# main.net
KiCad netlist of a schematic drawn in EAGLE
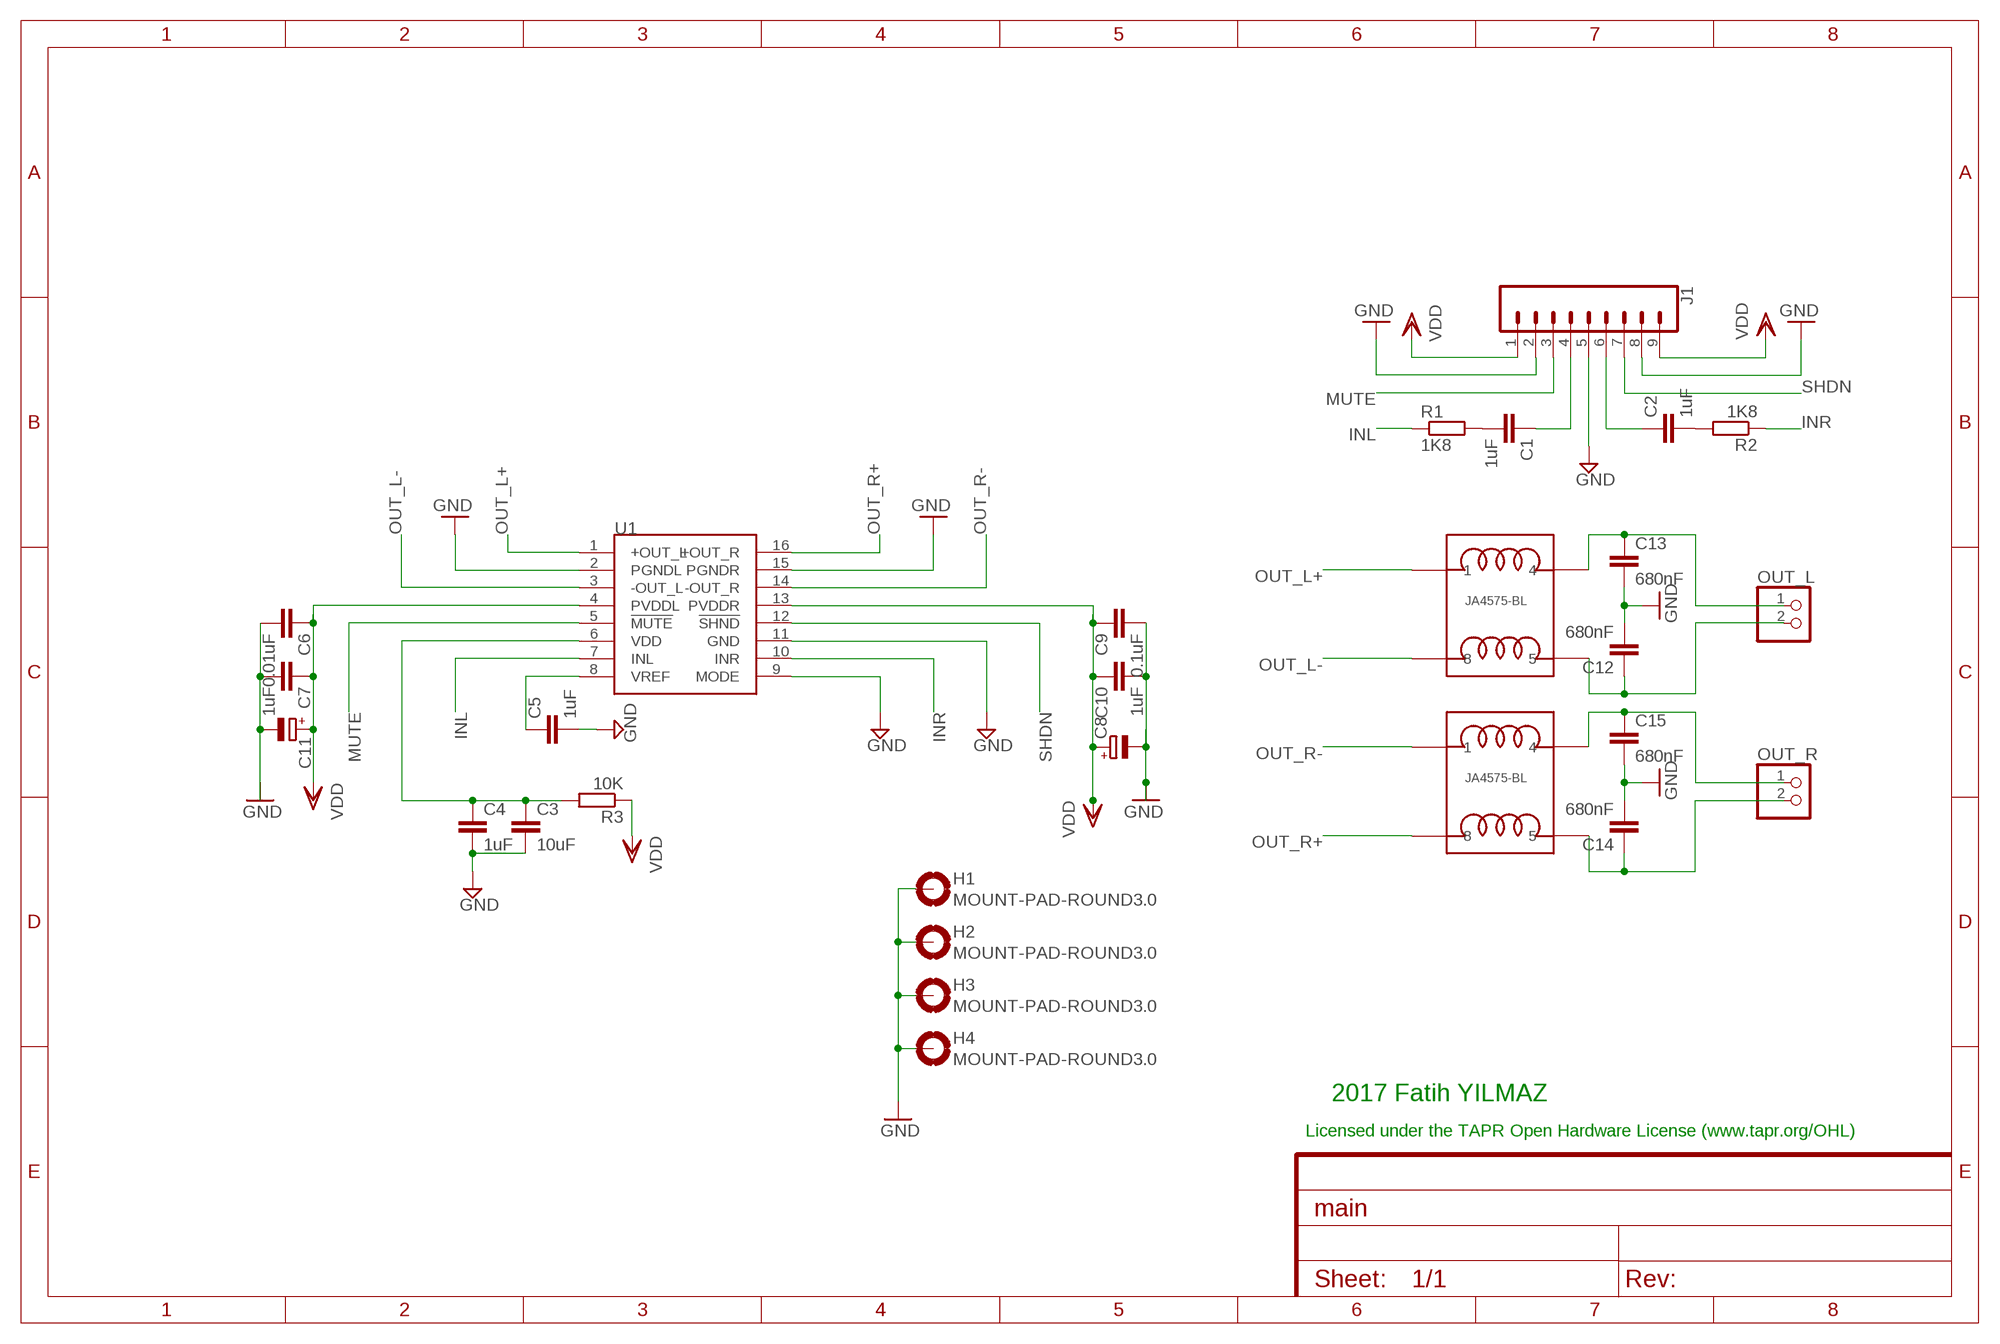
[diagram p0: schematic, sheet 1]

(export (version "E")
  (design (tool "Eeschema 10.0.6"))
  (components
    (comp (ref "C1")
      (value "1uF")
      (footprint "eagle-import:C1206")
      (fields (field (name "MPN") "C0603C105K4PACTU"))
      (libsource (lib "eagle-import") (part "C-EUC1206"))
    )
    (comp (ref "C2")
      (value "1uF")
      (footprint "eagle-import:C1206")
      (fields (field (name "MPN") "C0603C105K4PACTU"))
      (libsource (lib "eagle-import") (part "C-EUC1206"))
    )
    (comp (ref "C3")
      (value "10uF")
      (footprint "eagle-import:C1206")
      (libsource (lib "eagle-import") (part "C-EUC1206"))
    )
    (comp (ref "C4")
      (value "1uF")
      (footprint "eagle-import:C1206")
      (libsource (lib "eagle-import") (part "C-EUC1206"))
    )
    (comp (ref "C5")
      (value "1uF")
      (footprint "eagle-import:C1206")
      (libsource (lib "eagle-import") (part "C-EUC1206"))
    )
    (comp (ref "C6")
      (value "0.01uF")
      (footprint "eagle-import:C1206")
      (libsource (lib "eagle-import") (part "C-EUC1206"))
    )
    (comp (ref "C7")
      (value "1uF")
      (footprint "eagle-import:C1206")
      (libsource (lib "eagle-import") (part "C-EUC1206"))
    )
    (comp (ref "C8")
      (value "CPOL-EUE3.5-8")
      (footprint "eagle-import:E3,5-8")
      (libsource (lib "eagle-import") (part "CPOL-EUE3.5-8"))
    )
    (comp (ref "C9")
      (value "0.1uF")
      (footprint "eagle-import:C1206")
      (libsource (lib "eagle-import") (part "C-EUC1206"))
    )
    (comp (ref "C10")
      (value "1uF")
      (footprint "eagle-import:C1206")
      (libsource (lib "eagle-import") (part "C-EUC1206"))
    )
    (comp (ref "C11")
      (value "CPOL-EUE3.5-8")
      (footprint "eagle-import:E3,5-8")
      (libsource (lib "eagle-import") (part "CPOL-EUE3.5-8"))
    )
    (comp (ref "C12")
      (value "680nF")
      (footprint "eagle-import:C050-045X075")
      (libsource (lib "eagle-import") (part "C-EU050-045X075"))
    )
    (comp (ref "C13")
      (value "680nF")
      (footprint "eagle-import:C050-045X075")
      (libsource (lib "eagle-import") (part "C-EU050-045X075"))
    )
    (comp (ref "C14")
      (value "680nF")
      (footprint "eagle-import:C050-045X075")
      (libsource (lib "eagle-import") (part "C-EU050-045X075"))
    )
    (comp (ref "C15")
      (value "680nF")
      (footprint "eagle-import:C050-045X075")
      (libsource (lib "eagle-import") (part "C-EU050-045X075"))
    )
    (comp (ref "H1")
      (value "MOUNT-PAD-ROUND3.0")
      (footprint "eagle-import:3,0-PAD")
      (libsource (lib "eagle-import") (part "MOUNT-PAD-ROUND3.0"))
    )
    (comp (ref "H2")
      (value "MOUNT-PAD-ROUND3.0")
      (footprint "eagle-import:3,0-PAD")
      (libsource (lib "eagle-import") (part "MOUNT-PAD-ROUND3.0"))
    )
    (comp (ref "H3")
      (value "MOUNT-PAD-ROUND3.0")
      (footprint "eagle-import:3,0-PAD")
      (libsource (lib "eagle-import") (part "MOUNT-PAD-ROUND3.0"))
    )
    (comp (ref "H4")
      (value "MOUNT-PAD-ROUND3.0")
      (footprint "eagle-import:3,0-PAD")
      (libsource (lib "eagle-import") (part "MOUNT-PAD-ROUND3.0"))
    )
    (comp (ref "J1")
      (value "CONN_09NO_SILK")
      (footprint "eagle-import:1X09_NO_SILK")
      (libsource (lib "eagle-import") (part "CONN_09NO_SILK"))
    )
    (comp (ref "LEFT_COIL")
      (value "JA4575-BL")
      (footprint "eagle-import:JA4575-BL")
      (libsource (lib "eagle-import") (part "JA4575-BL"))
    )
    (comp (ref "OUT_L")
      (value "PINHD-1X2")
      (footprint "eagle-import:1X02")
      (libsource (lib "eagle-import") (part "PINHD-1X2"))
    )
    (comp (ref "OUT_R")
      (value "PINHD-1X2")
      (footprint "eagle-import:1X02")
      (libsource (lib "eagle-import") (part "PINHD-1X2"))
    )
    (comp (ref "R1")
      (value "1K8")
      (footprint "eagle-import:R1206")
      (libsource (lib "eagle-import") (part "R-EU_R1206"))
    )
    (comp (ref "R2")
      (value "1K8")
      (footprint "eagle-import:R1206")
      (libsource (lib "eagle-import") (part "R-EU_R1206"))
    )
    (comp (ref "R3")
      (value "10K")
      (footprint "eagle-import:R1206")
      (libsource (lib "eagle-import") (part "R-EU_R1206"))
    )
    (comp (ref "RIGHT_COIL")
      (value "JA4575-BL")
      (footprint "eagle-import:JA4575-BL")
      (libsource (lib "eagle-import") (part "JA4575-BL"))
    )
    (comp (ref "U1")
      (value "PAM8403")
      (footprint "eagle-import:SOP-16")
      (libsource (lib "eagle-import") (part "PAM8403"))
    )
  )
  (nets
    (net (code "1") (name "/INL") (class "Default")
      (node (ref "R1") (pin "1") (pinfunction "1_1") (pintype "passive"))
      (node (ref "U1") (pin "7") (pinfunction "INL_7") (pintype "input"))
    )
    (net (code "2") (name "/INR") (class "Default")
      (node (ref "R2") (pin "1") (pinfunction "1_1") (pintype "passive"))
      (node (ref "U1") (pin "10") (pinfunction "INR_10") (pintype "input"))
    )
    (net (code "3") (name "/MUTE") (class "Default")
      (node (ref "J1") (pin "3") (pinfunction "3_3") (pintype "passive"))
      (node (ref "U1") (pin "5") (pinfunction "~{MUTE}_5") (pintype "input"))
    )
    (net (code "4") (name "/OUT_L+") (class "Default")
      (node (ref "LEFT_COIL") (pin "1") (pinfunction "1_1") (pintype "bidirectional"))
      (node (ref "U1") (pin "1") (pinfunction "+OUT_L_1") (pintype "output"))
    )
    (net (code "5") (name "/OUT_L-") (class "Default")
      (node (ref "LEFT_COIL") (pin "8") (pinfunction "8_8") (pintype "bidirectional"))
      (node (ref "U1") (pin "3") (pinfunction "-OUT_L_3") (pintype "output"))
    )
    (net (code "6") (name "/OUT_R+") (class "Default")
      (node (ref "RIGHT_COIL") (pin "8") (pinfunction "8_8") (pintype "bidirectional"))
      (node (ref "U1") (pin "16") (pinfunction "+OUT_R_16") (pintype "output"))
    )
    (net (code "7") (name "/OUT_R-") (class "Default")
      (node (ref "RIGHT_COIL") (pin "1") (pinfunction "1_1") (pintype "bidirectional"))
      (node (ref "U1") (pin "14") (pinfunction "-OUT_R_14") (pintype "output"))
    )
    (net (code "8") (name "/SHDN") (class "Default")
      (node (ref "J1") (pin "7") (pinfunction "7_7") (pintype "passive"))
      (node (ref "U1") (pin "12") (pinfunction "~{SHND}_12") (pintype "output"))
    )
    (net (code "9") (name "GND") (class "Default")
      (node (ref "C10") (pin "2") (pinfunction "2_2") (pintype "passive"))
      (node (ref "C11") (pin "-") (pinfunction "-_-") (pintype "passive"))
      (node (ref "C12") (pin "2") (pinfunction "2_2") (pintype "passive"))
      (node (ref "C13") (pin "2") (pinfunction "2_2") (pintype "passive"))
      (node (ref "C14") (pin "2") (pinfunction "2_2") (pintype "passive"))
      (node (ref "C15") (pin "2") (pinfunction "2_2") (pintype "passive"))
      (node (ref "C3") (pin "2") (pinfunction "2_2") (pintype "passive"))
      (node (ref "C4") (pin "2") (pinfunction "2_2") (pintype "passive"))
      (node (ref "C5") (pin "2") (pinfunction "2_2") (pintype "passive"))
      (node (ref "C6") (pin "2") (pinfunction "2_2") (pintype "passive"))
      (node (ref "C7") (pin "2") (pinfunction "2_2") (pintype "passive"))
      (node (ref "C8") (pin "-") (pinfunction "-_-") (pintype "passive"))
      (node (ref "C9") (pin "2") (pinfunction "2_2") (pintype "passive"))
      (node (ref "H1") (pin "B3,0") (pinfunction "MOUNT_B3,0") (pintype "passive"))
      (node (ref "H2") (pin "B3,0") (pinfunction "MOUNT_B3,0") (pintype "passive"))
      (node (ref "H3") (pin "B3,0") (pinfunction "MOUNT_B3,0") (pintype "passive"))
      (node (ref "H4") (pin "B3,0") (pinfunction "MOUNT_B3,0") (pintype "passive"))
      (node (ref "J1") (pin "2") (pinfunction "2_2") (pintype "passive"))
      (node (ref "J1") (pin "5") (pinfunction "5_5") (pintype "passive"))
      (node (ref "J1") (pin "8") (pinfunction "8_8") (pintype "passive"))
      (node (ref "U1") (pin "11") (pinfunction "GND_11") (pintype "power_in"))
      (node (ref "U1") (pin "15") (pinfunction "PGNDR_15") (pintype "power_in"))
      (node (ref "U1") (pin "2") (pinfunction "PGNDL_2") (pintype "power_in"))
      (node (ref "U1") (pin "9") (pinfunction "MODE_9") (pintype "input"))
    )
    (net (code "10") (name "Net-(C1-Pad1)") (class "Default")
      (node (ref "C1") (pin "1") (pinfunction "1_1") (pintype "passive"))
      (node (ref "J1") (pin "4") (pinfunction "4_4") (pintype "passive"))
    )
    (net (code "11") (name "Net-(C1-Pad2)") (class "Default")
      (node (ref "C1") (pin "2") (pinfunction "2_2") (pintype "passive"))
      (node (ref "R1") (pin "2") (pinfunction "2_2") (pintype "passive"))
    )
    (net (code "12") (name "Net-(C2-Pad1)") (class "Default")
      (node (ref "C2") (pin "1") (pinfunction "1_1") (pintype "passive"))
      (node (ref "J1") (pin "6") (pinfunction "6_6") (pintype "passive"))
    )
    (net (code "13") (name "Net-(C2-Pad2)") (class "Default")
      (node (ref "C2") (pin "2") (pinfunction "2_2") (pintype "passive"))
      (node (ref "R2") (pin "2") (pinfunction "2_2") (pintype "passive"))
    )
    (net (code "14") (name "Net-(C12-Pad1)") (class "Default")
      (node (ref "C12") (pin "1") (pinfunction "1_1") (pintype "passive"))
      (node (ref "LEFT_COIL") (pin "5") (pinfunction "5_5") (pintype "bidirectional"))
      (node (ref "OUT_L") (pin "2") (pinfunction "2_2") (pintype "passive"))
    )
    (net (code "15") (name "Net-(C13-Pad1)") (class "Default")
      (node (ref "C13") (pin "1") (pinfunction "1_1") (pintype "passive"))
      (node (ref "LEFT_COIL") (pin "4") (pinfunction "4_4") (pintype "bidirectional"))
      (node (ref "OUT_L") (pin "1") (pinfunction "1_1") (pintype "passive"))
    )
    (net (code "16") (name "Net-(C14-Pad1)") (class "Default")
      (node (ref "C14") (pin "1") (pinfunction "1_1") (pintype "passive"))
      (node (ref "OUT_R") (pin "2") (pinfunction "2_2") (pintype "passive"))
      (node (ref "RIGHT_COIL") (pin "5") (pinfunction "5_5") (pintype "bidirectional"))
    )
    (net (code "17") (name "Net-(C15-Pad1)") (class "Default")
      (node (ref "C15") (pin "1") (pinfunction "1_1") (pintype "passive"))
      (node (ref "OUT_R") (pin "1") (pinfunction "1_1") (pintype "passive"))
      (node (ref "RIGHT_COIL") (pin "4") (pinfunction "4_4") (pintype "bidirectional"))
    )
    (net (code "18") (name "Net-(U1-VDD)") (class "Default")
      (node (ref "C3") (pin "1") (pinfunction "1_1") (pintype "passive"))
      (node (ref "C4") (pin "1") (pinfunction "1_1") (pintype "passive"))
      (node (ref "R3") (pin "2") (pinfunction "2_2") (pintype "passive"))
      (node (ref "U1") (pin "6") (pinfunction "VDD_6") (pintype "power_in"))
    )
    (net (code "19") (name "Net-(U1-VREF)") (class "Default")
      (node (ref "C5") (pin "1") (pinfunction "1_1") (pintype "passive"))
      (node (ref "U1") (pin "8") (pinfunction "VREF_8") (pintype "passive"))
    )
    (net (code "20") (name "VDD") (class "Default")
      (node (ref "C10") (pin "1") (pinfunction "1_1") (pintype "passive"))
      (node (ref "C11") (pin "+") (pinfunction "+_+") (pintype "passive"))
      (node (ref "C6") (pin "1") (pinfunction "1_1") (pintype "passive"))
      (node (ref "C7") (pin "1") (pinfunction "1_1") (pintype "passive"))
      (node (ref "C8") (pin "+") (pinfunction "+_+") (pintype "passive"))
      (node (ref "C9") (pin "1") (pinfunction "1_1") (pintype "passive"))
      (node (ref "J1") (pin "1") (pinfunction "1_1") (pintype "passive"))
      (node (ref "J1") (pin "9") (pinfunction "9_9") (pintype "passive"))
      (node (ref "R3") (pin "1") (pinfunction "1_1") (pintype "passive"))
      (node (ref "U1") (pin "13") (pinfunction "PVDDR_13") (pintype "power_in"))
      (node (ref "U1") (pin "4") (pinfunction "PVDDL_4") (pintype "power_in"))
    )
  )
)
